# moth8_v1.net
KiCad netlist of a schematic drawn in EAGLE
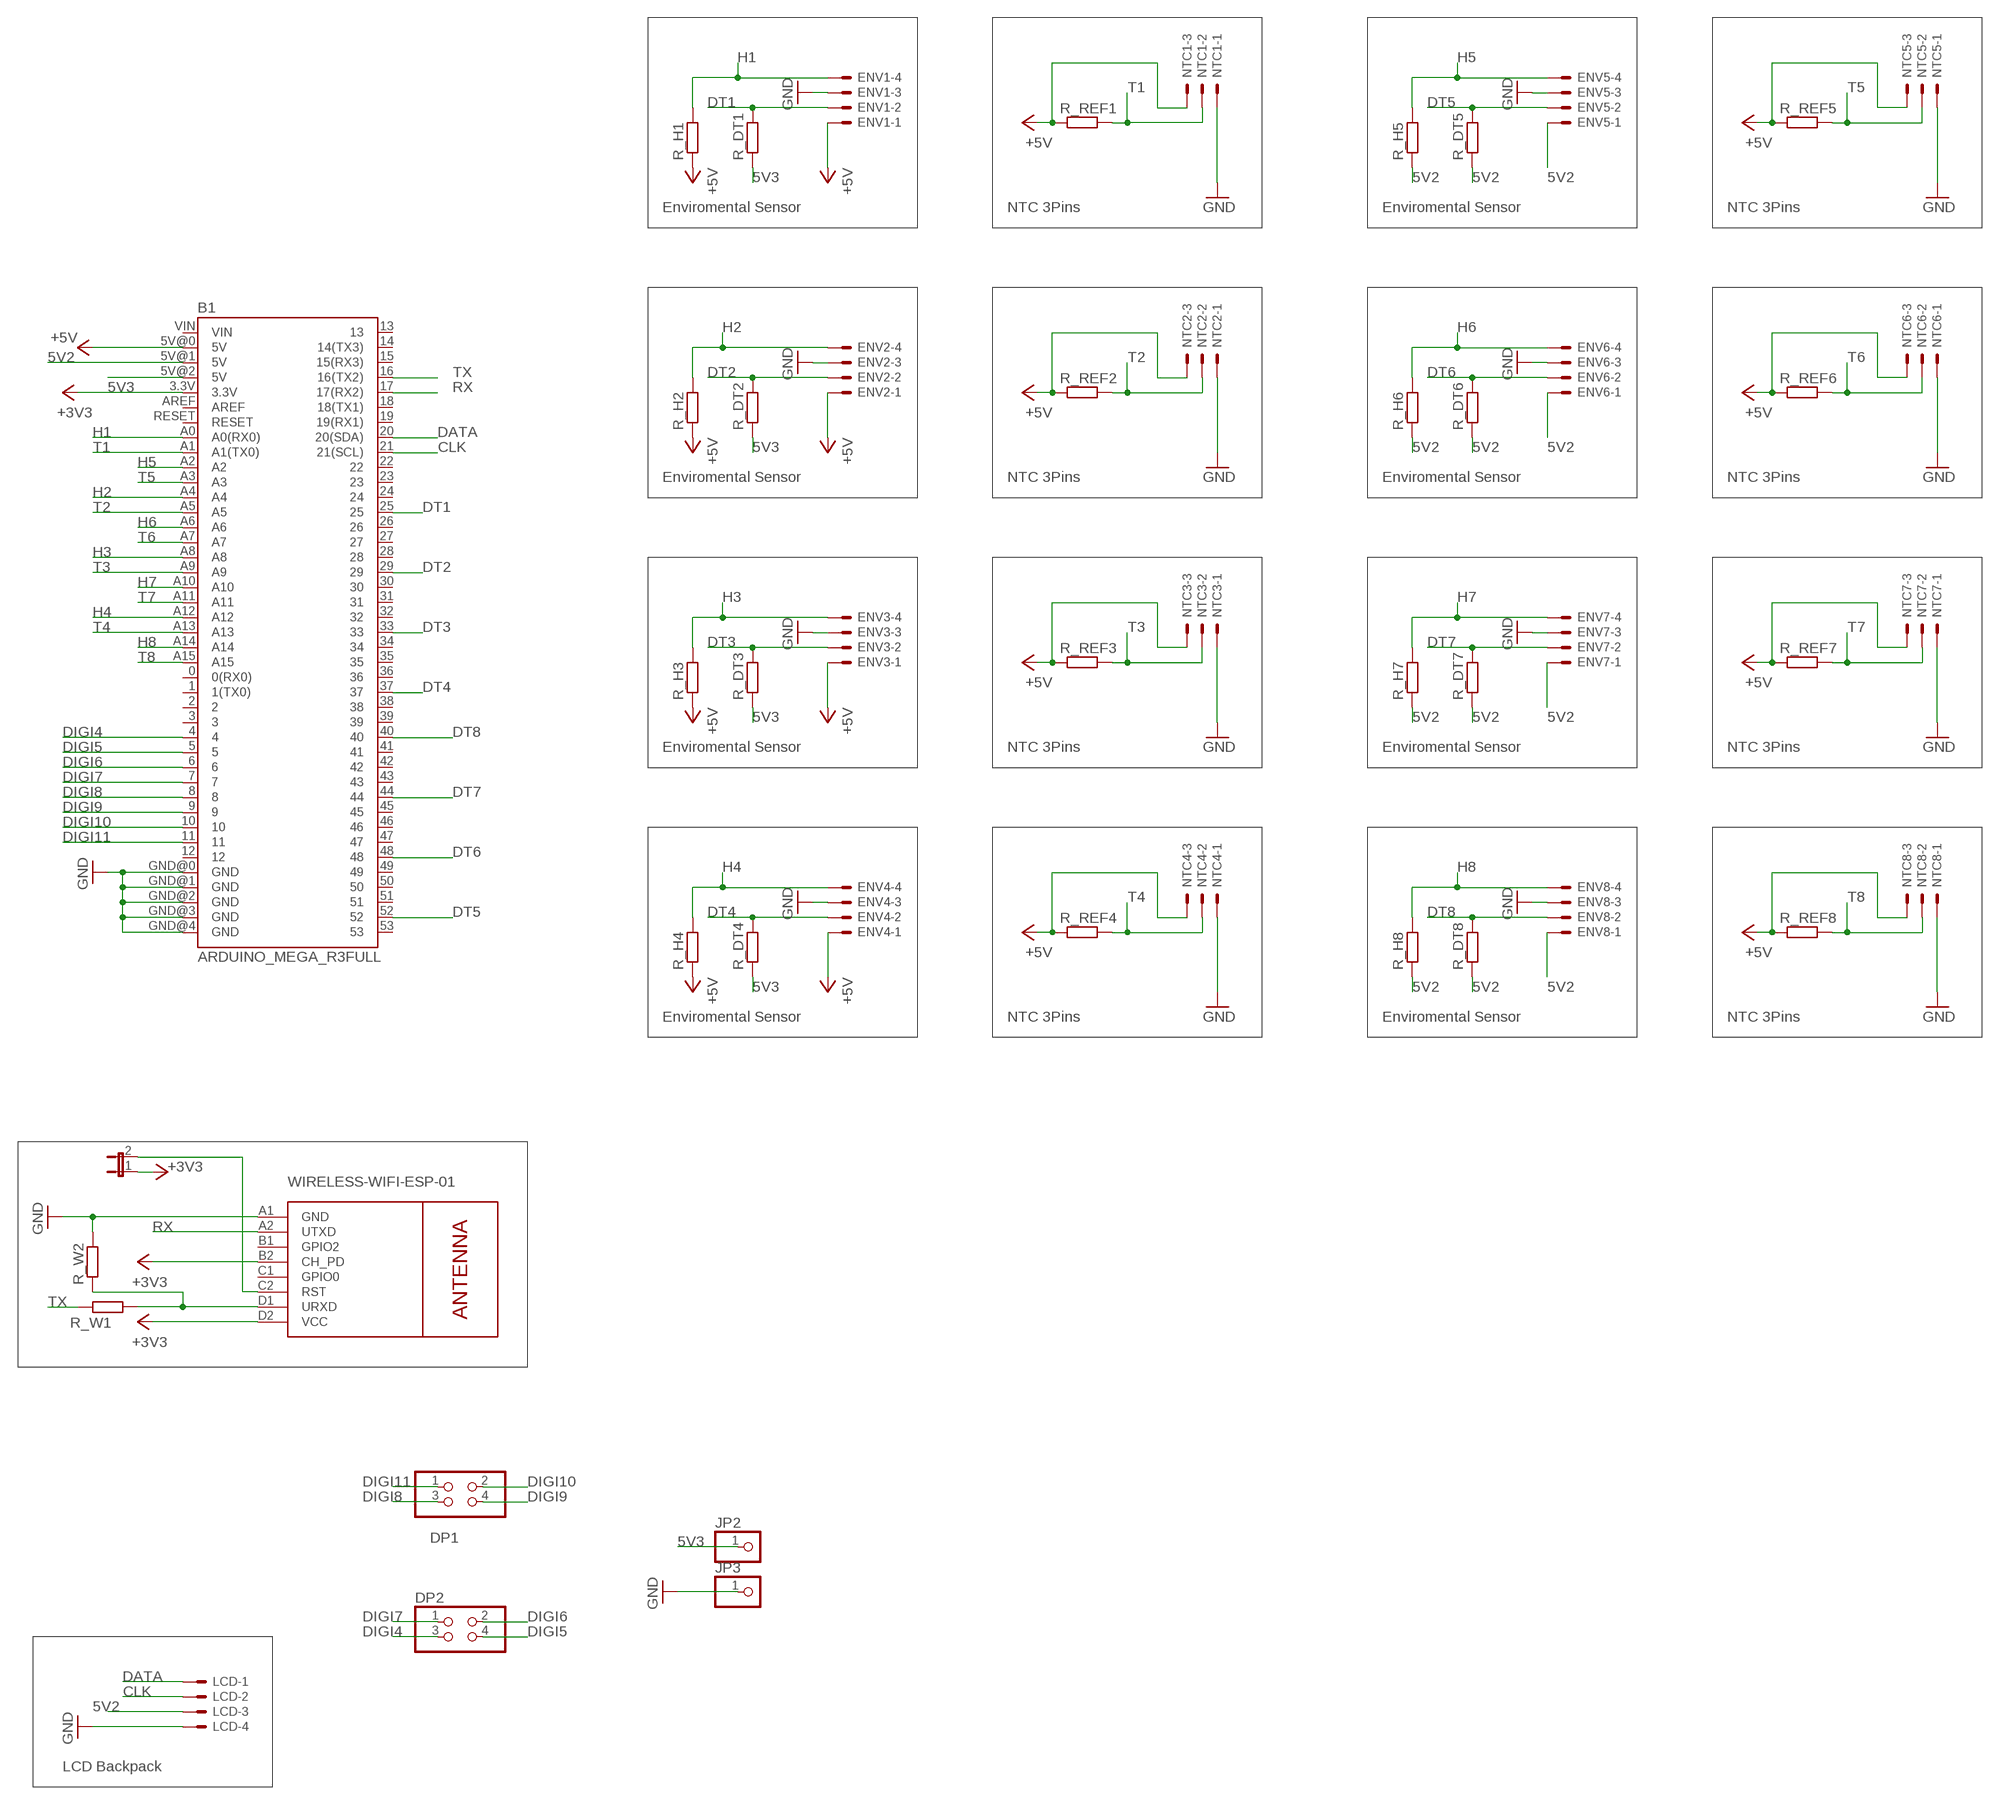
[diagram p0: schematic, sheet 1]

(export (version "E")
  (design (tool "Eeschema 10.0.6"))
  (components
    (comp (ref "B1")
      (value "ARDUINO_MEGA_R3FULL")
      (footprint "eagle-import:ARDUINO_MEGA")
      (libsource (lib "eagle-import") (part "ARDUINO_MEGA_R3FULL"))
    )
    (comp (ref "DP1")
      (value "PINHD-2X2")
      (footprint "eagle-import:2X02")
      (libsource (lib "eagle-import") (part "PINHD-2X2"))
    )
    (comp (ref "DP2")
      (value "PINHD-2X2")
      (footprint "eagle-import:2X02")
      (libsource (lib "eagle-import") (part "PINHD-2X2"))
    )
    (comp (ref "ENV1")
      (value "22-27-2041-04")
      (footprint "eagle-import:6410-04")
      (fields (field (name "MF") "MOLEX"))
      (libsource (lib "eagle-import") (part "22-?-0427-2041"))
    )
    (comp (ref "ENV2")
      (value "22-27-2041-04")
      (footprint "eagle-import:6410-04")
      (fields (field (name "MF") "MOLEX"))
      (libsource (lib "eagle-import") (part "22-?-0427-2041"))
    )
    (comp (ref "ENV3")
      (value "22-27-2041-04")
      (footprint "eagle-import:6410-04")
      (fields (field (name "MF") "MOLEX"))
      (libsource (lib "eagle-import") (part "22-?-0427-2041"))
    )
    (comp (ref "ENV4")
      (value "22-27-2041-04")
      (footprint "eagle-import:6410-04")
      (fields (field (name "MF") "MOLEX"))
      (libsource (lib "eagle-import") (part "22-?-0427-2041"))
    )
    (comp (ref "ENV5")
      (value "22-27-2041-04")
      (footprint "eagle-import:6410-04")
      (fields (field (name "MF") "MOLEX"))
      (libsource (lib "eagle-import") (part "22-?-0427-2041"))
    )
    (comp (ref "ENV6")
      (value "22-27-2041-04")
      (footprint "eagle-import:6410-04")
      (fields (field (name "MF") "MOLEX"))
      (libsource (lib "eagle-import") (part "22-?-0427-2041"))
    )
    (comp (ref "ENV7")
      (value "22-27-2041-04")
      (footprint "eagle-import:6410-04")
      (fields (field (name "MF") "MOLEX"))
      (libsource (lib "eagle-import") (part "22-?-0427-2041"))
    )
    (comp (ref "ENV8")
      (value "22-27-2041-04")
      (footprint "eagle-import:6410-04")
      (fields (field (name "MF") "MOLEX"))
      (libsource (lib "eagle-import") (part "22-?-0427-2041"))
    )
    (comp (ref "ESP-01")
      (value "WIRELESS-WIFI-ESP-01")
      (footprint "eagle-import:WIRELESS-WIFI-ESP-01")
      (libsource (lib "eagle-import") (part "WIRELESS-WIFI-ESP-01"))
    )
    (comp (ref "JP1")
      (value "JP1E")
      (footprint "eagle-import:JP1")
      (libsource (lib "eagle-import") (part "JP1E"))
    )
    (comp (ref "JP2")
      (value "PINHD-1X1")
      (footprint "eagle-import:1X01")
      (libsource (lib "eagle-import") (part "PINHD-1X1"))
    )
    (comp (ref "JP3")
      (value "PINHD-1X1")
      (footprint "eagle-import:1X01")
      (libsource (lib "eagle-import") (part "PINHD-1X1"))
    )
    (comp (ref "LCD")
      (value "22-27-2041-04")
      (footprint "eagle-import:6410-04")
      (fields (field (name "MF") "MOLEX"))
      (libsource (lib "eagle-import") (part "22-?-0427-2041"))
    )
    (comp (ref "NTC1")
      (value "22-27-2031-03")
      (footprint "eagle-import:6410-03")
      (fields (field (name "MF") "MOLEX"))
      (libsource (lib "eagle-import") (part "22-?-0327-2031"))
    )
    (comp (ref "NTC2")
      (value "22-27-2031-03")
      (footprint "eagle-import:6410-03")
      (fields (field (name "MF") "MOLEX"))
      (libsource (lib "eagle-import") (part "22-?-0327-2031"))
    )
    (comp (ref "NTC3")
      (value "22-27-2031-03")
      (footprint "eagle-import:6410-03")
      (fields (field (name "MF") "MOLEX"))
      (libsource (lib "eagle-import") (part "22-?-0327-2031"))
    )
    (comp (ref "NTC4")
      (value "22-27-2031-03")
      (footprint "eagle-import:6410-03")
      (fields (field (name "MF") "MOLEX"))
      (libsource (lib "eagle-import") (part "22-?-0327-2031"))
    )
    (comp (ref "NTC5")
      (value "22-27-2031-03")
      (footprint "eagle-import:6410-03")
      (fields (field (name "MF") "MOLEX"))
      (libsource (lib "eagle-import") (part "22-?-0327-2031"))
    )
    (comp (ref "NTC6")
      (value "22-27-2031-03")
      (footprint "eagle-import:6410-03")
      (fields (field (name "MF") "MOLEX"))
      (libsource (lib "eagle-import") (part "22-?-0327-2031"))
    )
    (comp (ref "NTC7")
      (value "22-27-2031-03")
      (footprint "eagle-import:6410-03")
      (fields (field (name "MF") "MOLEX"))
      (libsource (lib "eagle-import") (part "22-?-0327-2031"))
    )
    (comp (ref "NTC8")
      (value "22-27-2031-03")
      (footprint "eagle-import:6410-03")
      (fields (field (name "MF") "MOLEX"))
      (libsource (lib "eagle-import") (part "22-?-0327-2031"))
    )
    (comp (ref "R_DT1")
      (value "R-EU_R1206")
      (footprint "eagle-import:R1206")
      (libsource (lib "eagle-import") (part "R-EU_R1206"))
    )
    (comp (ref "R_DT2")
      (value "R-EU_R1206")
      (footprint "eagle-import:R1206")
      (libsource (lib "eagle-import") (part "R-EU_R1206"))
    )
    (comp (ref "R_DT3")
      (value "R-EU_R1206")
      (footprint "eagle-import:R1206")
      (libsource (lib "eagle-import") (part "R-EU_R1206"))
    )
    (comp (ref "R_DT4")
      (value "R-EU_R1206")
      (footprint "eagle-import:R1206")
      (libsource (lib "eagle-import") (part "R-EU_R1206"))
    )
    (comp (ref "R_DT5")
      (value "R-EU_R1206")
      (footprint "eagle-import:R1206")
      (libsource (lib "eagle-import") (part "R-EU_R1206"))
    )
    (comp (ref "R_DT6")
      (value "R-EU_R1206")
      (footprint "eagle-import:R1206")
      (libsource (lib "eagle-import") (part "R-EU_R1206"))
    )
    (comp (ref "R_DT7")
      (value "R-EU_R1206")
      (footprint "eagle-import:R1206")
      (libsource (lib "eagle-import") (part "R-EU_R1206"))
    )
    (comp (ref "R_DT8")
      (value "R-EU_R1206")
      (footprint "eagle-import:R1206")
      (libsource (lib "eagle-import") (part "R-EU_R1206"))
    )
    (comp (ref "R_H1")
      (value "R-EU_R1206")
      (footprint "eagle-import:R1206")
      (libsource (lib "eagle-import") (part "R-EU_R1206"))
    )
    (comp (ref "R_H2")
      (value "R-EU_R1206")
      (footprint "eagle-import:R1206")
      (libsource (lib "eagle-import") (part "R-EU_R1206"))
    )
    (comp (ref "R_H3")
      (value "R-EU_R1206")
      (footprint "eagle-import:R1206")
      (libsource (lib "eagle-import") (part "R-EU_R1206"))
    )
    (comp (ref "R_H4")
      (value "R-EU_R1206")
      (footprint "eagle-import:R1206")
      (libsource (lib "eagle-import") (part "R-EU_R1206"))
    )
    (comp (ref "R_H5")
      (value "R-EU_R1206")
      (footprint "eagle-import:R1206")
      (libsource (lib "eagle-import") (part "R-EU_R1206"))
    )
    (comp (ref "R_H6")
      (value "R-EU_R1206")
      (footprint "eagle-import:R1206")
      (libsource (lib "eagle-import") (part "R-EU_R1206"))
    )
    (comp (ref "R_H7")
      (value "R-EU_R1206")
      (footprint "eagle-import:R1206")
      (libsource (lib "eagle-import") (part "R-EU_R1206"))
    )
    (comp (ref "R_H8")
      (value "R-EU_R1206")
      (footprint "eagle-import:R1206")
      (libsource (lib "eagle-import") (part "R-EU_R1206"))
    )
    (comp (ref "R_REF1")
      (value "R-EU_R1206")
      (footprint "eagle-import:R1206")
      (libsource (lib "eagle-import") (part "R-EU_R1206"))
    )
    (comp (ref "R_REF2")
      (value "R-EU_R1206")
      (footprint "eagle-import:R1206")
      (libsource (lib "eagle-import") (part "R-EU_R1206"))
    )
    (comp (ref "R_REF3")
      (value "R-EU_R1206")
      (footprint "eagle-import:R1206")
      (libsource (lib "eagle-import") (part "R-EU_R1206"))
    )
    (comp (ref "R_REF4")
      (value "R-EU_R1206")
      (footprint "eagle-import:R1206")
      (libsource (lib "eagle-import") (part "R-EU_R1206"))
    )
    (comp (ref "R_REF5")
      (value "R-EU_R1206")
      (footprint "eagle-import:R1206")
      (libsource (lib "eagle-import") (part "R-EU_R1206"))
    )
    (comp (ref "R_REF6")
      (value "R-EU_R1206")
      (footprint "eagle-import:R1206")
      (libsource (lib "eagle-import") (part "R-EU_R1206"))
    )
    (comp (ref "R_REF7")
      (value "R-EU_R1206")
      (footprint "eagle-import:R1206")
      (libsource (lib "eagle-import") (part "R-EU_R1206"))
    )
    (comp (ref "R_REF8")
      (value "R-EU_R1206")
      (footprint "eagle-import:R1206")
      (libsource (lib "eagle-import") (part "R-EU_R1206"))
    )
    (comp (ref "R_W1")
      (value "R-EU_R1206")
      (footprint "eagle-import:R1206")
      (libsource (lib "eagle-import") (part "R-EU_R1206"))
    )
    (comp (ref "R_W2")
      (value "R-EU_R1206")
      (footprint "eagle-import:R1206")
      (libsource (lib "eagle-import") (part "R-EU_R1206"))
    )
  )
  (nets
    (net (code "1") (name "+3V3") (class "Default")
      (node (ref "B1") (pin "3.3V") (pinfunction "3.3V_3.3V") (pintype "bidirectional"))
      (node (ref "ESP-01") (pin "B2") (pinfunction "CH_PD_B2") (pintype "bidirectional"))
      (node (ref "ESP-01") (pin "D2") (pinfunction "VCC_D2") (pintype "power_in"))
      (node (ref "JP1") (pin "1") (pinfunction "1_1") (pintype "passive"))
    )
    (net (code "2") (name "+5V") (class "Default")
      (node (ref "B1") (pin "5V@0") (pinfunction "5V_5V@0") (pintype "bidirectional"))
      (node (ref "ENV1") (pin "1") (pinfunction "S_1") (pintype "passive"))
      (node (ref "ENV2") (pin "1") (pinfunction "S_1") (pintype "passive"))
      (node (ref "ENV3") (pin "1") (pinfunction "S_1") (pintype "passive"))
      (node (ref "ENV4") (pin "1") (pinfunction "S_1") (pintype "passive"))
      (node (ref "NTC1") (pin "3") (pinfunction "S_3") (pintype "passive"))
      (node (ref "NTC2") (pin "3") (pinfunction "S_3") (pintype "passive"))
      (node (ref "NTC3") (pin "3") (pinfunction "S_3") (pintype "passive"))
      (node (ref "NTC4") (pin "3") (pinfunction "S_3") (pintype "passive"))
      (node (ref "NTC5") (pin "3") (pinfunction "S_3") (pintype "passive"))
      (node (ref "NTC6") (pin "3") (pinfunction "S_3") (pintype "passive"))
      (node (ref "NTC7") (pin "3") (pinfunction "S_3") (pintype "passive"))
      (node (ref "NTC8") (pin "3") (pinfunction "S_3") (pintype "passive"))
      (node (ref "R_H1") (pin "1") (pinfunction "1_1") (pintype "passive"))
      (node (ref "R_H2") (pin "1") (pinfunction "1_1") (pintype "passive"))
      (node (ref "R_H3") (pin "1") (pinfunction "1_1") (pintype "passive"))
      (node (ref "R_H4") (pin "1") (pinfunction "1_1") (pintype "passive"))
      (node (ref "R_REF1") (pin "1") (pinfunction "1_1") (pintype "passive"))
      (node (ref "R_REF2") (pin "1") (pinfunction "1_1") (pintype "passive"))
      (node (ref "R_REF3") (pin "1") (pinfunction "1_1") (pintype "passive"))
      (node (ref "R_REF4") (pin "1") (pinfunction "1_1") (pintype "passive"))
      (node (ref "R_REF5") (pin "1") (pinfunction "1_1") (pintype "passive"))
      (node (ref "R_REF6") (pin "1") (pinfunction "1_1") (pintype "passive"))
      (node (ref "R_REF7") (pin "1") (pinfunction "1_1") (pintype "passive"))
      (node (ref "R_REF8") (pin "1") (pinfunction "1_1") (pintype "passive"))
    )
    (net (code "3") (name "/5V2") (class "Default")
      (node (ref "B1") (pin "5V@1") (pinfunction "5V_5V@1") (pintype "bidirectional"))
      (node (ref "ENV5") (pin "1") (pinfunction "S_1") (pintype "passive"))
      (node (ref "ENV6") (pin "1") (pinfunction "S_1") (pintype "passive"))
      (node (ref "ENV7") (pin "1") (pinfunction "S_1") (pintype "passive"))
      (node (ref "ENV8") (pin "1") (pinfunction "S_1") (pintype "passive"))
      (node (ref "LCD") (pin "3") (pinfunction "S_3") (pintype "passive"))
      (node (ref "R_DT5") (pin "1") (pinfunction "1_1") (pintype "passive"))
      (node (ref "R_DT6") (pin "1") (pinfunction "1_1") (pintype "passive"))
      (node (ref "R_DT7") (pin "1") (pinfunction "1_1") (pintype "passive"))
      (node (ref "R_DT8") (pin "1") (pinfunction "1_1") (pintype "passive"))
      (node (ref "R_H5") (pin "1") (pinfunction "1_1") (pintype "passive"))
      (node (ref "R_H6") (pin "1") (pinfunction "1_1") (pintype "passive"))
      (node (ref "R_H7") (pin "1") (pinfunction "1_1") (pintype "passive"))
      (node (ref "R_H8") (pin "1") (pinfunction "1_1") (pintype "passive"))
    )
    (net (code "4") (name "/5V3") (class "Default")
      (node (ref "B1") (pin "5V@2") (pinfunction "5V_5V@2") (pintype "bidirectional"))
      (node (ref "JP2") (pin "1") (pinfunction "1_1") (pintype "passive"))
      (node (ref "R_DT1") (pin "1") (pinfunction "1_1") (pintype "passive"))
      (node (ref "R_DT2") (pin "1") (pinfunction "1_1") (pintype "passive"))
      (node (ref "R_DT3") (pin "1") (pinfunction "1_1") (pintype "passive"))
      (node (ref "R_DT4") (pin "1") (pinfunction "1_1") (pintype "passive"))
    )
    (net (code "5") (name "/CLK") (class "Default")
      (node (ref "B1") (pin "21") (pinfunction "21(SCL)_21") (pintype "bidirectional"))
      (node (ref "LCD") (pin "2") (pinfunction "S_2") (pintype "passive"))
    )
    (net (code "6") (name "/DATA") (class "Default")
      (node (ref "B1") (pin "20") (pinfunction "20(SDA)_20") (pintype "bidirectional"))
      (node (ref "LCD") (pin "1") (pinfunction "S_1") (pintype "passive"))
    )
    (net (code "7") (name "/DIGI4") (class "Default")
      (node (ref "B1") (pin "4") (pinfunction "4_4") (pintype "bidirectional"))
      (node (ref "DP2") (pin "3") (pinfunction "3_3") (pintype "passive"))
    )
    (net (code "8") (name "/DIGI5") (class "Default")
      (node (ref "B1") (pin "5") (pinfunction "5_5") (pintype "bidirectional"))
      (node (ref "DP2") (pin "4") (pinfunction "4_4") (pintype "passive"))
    )
    (net (code "9") (name "/DIGI6") (class "Default")
      (node (ref "B1") (pin "6") (pinfunction "6_6") (pintype "bidirectional"))
      (node (ref "DP2") (pin "2") (pinfunction "2_2") (pintype "passive"))
    )
    (net (code "10") (name "/DIGI7") (class "Default")
      (node (ref "B1") (pin "7") (pinfunction "7_7") (pintype "bidirectional"))
      (node (ref "DP2") (pin "1") (pinfunction "1_1") (pintype "passive"))
    )
    (net (code "11") (name "/DIGI8") (class "Default")
      (node (ref "B1") (pin "8") (pinfunction "8_8") (pintype "bidirectional"))
      (node (ref "DP1") (pin "3") (pinfunction "3_3") (pintype "passive"))
    )
    (net (code "12") (name "/DIGI9") (class "Default")
      (node (ref "B1") (pin "9") (pinfunction "9_9") (pintype "bidirectional"))
      (node (ref "DP1") (pin "4") (pinfunction "4_4") (pintype "passive"))
    )
    (net (code "13") (name "/DIGI10") (class "Default")
      (node (ref "B1") (pin "10") (pinfunction "10_10") (pintype "bidirectional"))
      (node (ref "DP1") (pin "2") (pinfunction "2_2") (pintype "passive"))
    )
    (net (code "14") (name "/DIGI11") (class "Default")
      (node (ref "B1") (pin "11") (pinfunction "11_11") (pintype "bidirectional"))
      (node (ref "DP1") (pin "1") (pinfunction "1_1") (pintype "passive"))
    )
    (net (code "15") (name "/DT1") (class "Default")
      (node (ref "B1") (pin "25") (pinfunction "25_25") (pintype "bidirectional"))
      (node (ref "ENV1") (pin "2") (pinfunction "S_2") (pintype "passive"))
      (node (ref "R_DT1") (pin "2") (pinfunction "2_2") (pintype "passive"))
    )
    (net (code "16") (name "/DT2") (class "Default")
      (node (ref "B1") (pin "29") (pinfunction "29_29") (pintype "bidirectional"))
      (node (ref "ENV2") (pin "2") (pinfunction "S_2") (pintype "passive"))
      (node (ref "R_DT2") (pin "2") (pinfunction "2_2") (pintype "passive"))
    )
    (net (code "17") (name "/DT3") (class "Default")
      (node (ref "B1") (pin "33") (pinfunction "33_33") (pintype "bidirectional"))
      (node (ref "ENV3") (pin "2") (pinfunction "S_2") (pintype "passive"))
      (node (ref "R_DT3") (pin "2") (pinfunction "2_2") (pintype "passive"))
    )
    (net (code "18") (name "/DT4") (class "Default")
      (node (ref "B1") (pin "37") (pinfunction "37_37") (pintype "bidirectional"))
      (node (ref "ENV4") (pin "2") (pinfunction "S_2") (pintype "passive"))
      (node (ref "R_DT4") (pin "2") (pinfunction "2_2") (pintype "passive"))
    )
    (net (code "19") (name "/DT5") (class "Default")
      (node (ref "B1") (pin "52") (pinfunction "52_52") (pintype "bidirectional"))
      (node (ref "ENV5") (pin "2") (pinfunction "S_2") (pintype "passive"))
      (node (ref "R_DT5") (pin "2") (pinfunction "2_2") (pintype "passive"))
    )
    (net (code "20") (name "/DT6") (class "Default")
      (node (ref "B1") (pin "48") (pinfunction "48_48") (pintype "bidirectional"))
      (node (ref "ENV6") (pin "2") (pinfunction "S_2") (pintype "passive"))
      (node (ref "R_DT6") (pin "2") (pinfunction "2_2") (pintype "passive"))
    )
    (net (code "21") (name "/DT7") (class "Default")
      (node (ref "B1") (pin "44") (pinfunction "44_44") (pintype "bidirectional"))
      (node (ref "ENV7") (pin "2") (pinfunction "S_2") (pintype "passive"))
      (node (ref "R_DT7") (pin "2") (pinfunction "2_2") (pintype "passive"))
    )
    (net (code "22") (name "/DT8") (class "Default")
      (node (ref "B1") (pin "40") (pinfunction "40_40") (pintype "bidirectional"))
      (node (ref "ENV8") (pin "2") (pinfunction "S_2") (pintype "passive"))
      (node (ref "R_DT8") (pin "2") (pinfunction "2_2") (pintype "passive"))
    )
    (net (code "23") (name "/H1") (class "Default")
      (node (ref "B1") (pin "A0") (pinfunction "A0(RX0)_A0") (pintype "bidirectional"))
      (node (ref "ENV1") (pin "4") (pinfunction "S_4") (pintype "passive"))
      (node (ref "R_H1") (pin "2") (pinfunction "2_2") (pintype "passive"))
    )
    (net (code "24") (name "/H2") (class "Default")
      (node (ref "B1") (pin "A4") (pinfunction "A4_A4") (pintype "bidirectional"))
      (node (ref "ENV2") (pin "4") (pinfunction "S_4") (pintype "passive"))
      (node (ref "R_H2") (pin "2") (pinfunction "2_2") (pintype "passive"))
    )
    (net (code "25") (name "/H3") (class "Default")
      (node (ref "B1") (pin "A8") (pinfunction "A8_A8") (pintype "bidirectional"))
      (node (ref "ENV3") (pin "4") (pinfunction "S_4") (pintype "passive"))
      (node (ref "R_H3") (pin "2") (pinfunction "2_2") (pintype "passive"))
    )
    (net (code "26") (name "/H4") (class "Default")
      (node (ref "B1") (pin "A12") (pinfunction "A12_A12") (pintype "bidirectional"))
      (node (ref "ENV4") (pin "4") (pinfunction "S_4") (pintype "passive"))
      (node (ref "R_H4") (pin "2") (pinfunction "2_2") (pintype "passive"))
    )
    (net (code "27") (name "/H5") (class "Default")
      (node (ref "B1") (pin "A2") (pinfunction "A2_A2") (pintype "bidirectional"))
      (node (ref "ENV5") (pin "4") (pinfunction "S_4") (pintype "passive"))
      (node (ref "R_H5") (pin "2") (pinfunction "2_2") (pintype "passive"))
    )
    (net (code "28") (name "/H6") (class "Default")
      (node (ref "B1") (pin "A6") (pinfunction "A6_A6") (pintype "bidirectional"))
      (node (ref "ENV6") (pin "4") (pinfunction "S_4") (pintype "passive"))
      (node (ref "R_H6") (pin "2") (pinfunction "2_2") (pintype "passive"))
    )
    (net (code "29") (name "/H7") (class "Default")
      (node (ref "B1") (pin "A10") (pinfunction "A10_A10") (pintype "bidirectional"))
      (node (ref "ENV7") (pin "4") (pinfunction "S_4") (pintype "passive"))
      (node (ref "R_H7") (pin "2") (pinfunction "2_2") (pintype "passive"))
    )
    (net (code "30") (name "/H8") (class "Default")
      (node (ref "B1") (pin "A14") (pinfunction "A14_A14") (pintype "bidirectional"))
      (node (ref "ENV8") (pin "4") (pinfunction "S_4") (pintype "passive"))
      (node (ref "R_H8") (pin "2") (pinfunction "2_2") (pintype "passive"))
    )
    (net (code "31") (name "/RX") (class "Default")
      (node (ref "B1") (pin "17") (pinfunction "17(RX2)_17") (pintype "bidirectional"))
      (node (ref "ESP-01") (pin "A2") (pinfunction "UTXD_A2") (pintype "bidirectional"))
    )
    (net (code "32") (name "/T1") (class "Default")
      (node (ref "B1") (pin "A1") (pinfunction "A1(TX0)_A1") (pintype "bidirectional"))
      (node (ref "NTC1") (pin "2") (pinfunction "S_2") (pintype "passive"))
      (node (ref "R_REF1") (pin "2") (pinfunction "2_2") (pintype "passive"))
    )
    (net (code "33") (name "/T2") (class "Default")
      (node (ref "B1") (pin "A5") (pinfunction "A5_A5") (pintype "bidirectional"))
      (node (ref "NTC2") (pin "2") (pinfunction "S_2") (pintype "passive"))
      (node (ref "R_REF2") (pin "2") (pinfunction "2_2") (pintype "passive"))
    )
    (net (code "34") (name "/T3") (class "Default")
      (node (ref "B1") (pin "A9") (pinfunction "A9_A9") (pintype "bidirectional"))
      (node (ref "NTC3") (pin "2") (pinfunction "S_2") (pintype "passive"))
      (node (ref "R_REF3") (pin "2") (pinfunction "2_2") (pintype "passive"))
    )
    (net (code "35") (name "/T4") (class "Default")
      (node (ref "B1") (pin "A13") (pinfunction "A13_A13") (pintype "bidirectional"))
      (node (ref "NTC4") (pin "2") (pinfunction "S_2") (pintype "passive"))
      (node (ref "R_REF4") (pin "2") (pinfunction "2_2") (pintype "passive"))
    )
    (net (code "36") (name "/T5") (class "Default")
      (node (ref "B1") (pin "A3") (pinfunction "A3_A3") (pintype "bidirectional"))
      (node (ref "NTC5") (pin "2") (pinfunction "S_2") (pintype "passive"))
      (node (ref "R_REF5") (pin "2") (pinfunction "2_2") (pintype "passive"))
    )
    (net (code "37") (name "/T6") (class "Default")
      (node (ref "B1") (pin "A7") (pinfunction "A7_A7") (pintype "bidirectional"))
      (node (ref "NTC6") (pin "2") (pinfunction "S_2") (pintype "passive"))
      (node (ref "R_REF6") (pin "2") (pinfunction "2_2") (pintype "passive"))
    )
    (net (code "38") (name "/T7") (class "Default")
      (node (ref "B1") (pin "A11") (pinfunction "A11_A11") (pintype "bidirectional"))
      (node (ref "NTC7") (pin "2") (pinfunction "S_2") (pintype "passive"))
      (node (ref "R_REF7") (pin "2") (pinfunction "2_2") (pintype "passive"))
    )
    (net (code "39") (name "/T8") (class "Default")
      (node (ref "B1") (pin "A15") (pinfunction "A15_A15") (pintype "bidirectional"))
      (node (ref "NTC8") (pin "2") (pinfunction "S_2") (pintype "passive"))
      (node (ref "R_REF8") (pin "2") (pinfunction "2_2") (pintype "passive"))
    )
    (net (code "40") (name "/TX") (class "Default")
      (node (ref "B1") (pin "16") (pinfunction "16(TX2)_16") (pintype "bidirectional"))
      (node (ref "R_W1") (pin "1") (pinfunction "1_1") (pintype "passive"))
    )
    (net (code "41") (name "GND") (class "Default")
      (node (ref "B1") (pin "GND@0") (pinfunction "GND_GND@0") (pintype "bidirectional"))
      (node (ref "B1") (pin "GND@1") (pinfunction "GND_GND@1") (pintype "bidirectional"))
      (node (ref "B1") (pin "GND@2") (pinfunction "GND_GND@2") (pintype "bidirectional"))
      (node (ref "B1") (pin "GND@3") (pinfunction "GND_GND@3") (pintype "bidirectional"))
      (node (ref "B1") (pin "GND@4") (pinfunction "GND_GND@4") (pintype "bidirectional"))
      (node (ref "ENV1") (pin "3") (pinfunction "S_3") (pintype "passive"))
      (node (ref "ENV2") (pin "3") (pinfunction "S_3") (pintype "passive"))
      (node (ref "ENV3") (pin "3") (pinfunction "S_3") (pintype "passive"))
      (node (ref "ENV4") (pin "3") (pinfunction "S_3") (pintype "passive"))
      (node (ref "ENV5") (pin "3") (pinfunction "S_3") (pintype "passive"))
      (node (ref "ENV6") (pin "3") (pinfunction "S_3") (pintype "passive"))
      (node (ref "ENV7") (pin "3") (pinfunction "S_3") (pintype "passive"))
      (node (ref "ENV8") (pin "3") (pinfunction "S_3") (pintype "passive"))
      (node (ref "ESP-01") (pin "A1") (pinfunction "GND_A1") (pintype "power_in"))
      (node (ref "JP3") (pin "1") (pinfunction "1_1") (pintype "passive"))
      (node (ref "LCD") (pin "4") (pinfunction "S_4") (pintype "passive"))
      (node (ref "NTC1") (pin "1") (pinfunction "S_1") (pintype "passive"))
      (node (ref "NTC2") (pin "1") (pinfunction "S_1") (pintype "passive"))
      (node (ref "NTC3") (pin "1") (pinfunction "S_1") (pintype "passive"))
      (node (ref "NTC4") (pin "1") (pinfunction "S_1") (pintype "passive"))
      (node (ref "NTC5") (pin "1") (pinfunction "S_1") (pintype "passive"))
      (node (ref "NTC6") (pin "1") (pinfunction "S_1") (pintype "passive"))
      (node (ref "NTC7") (pin "1") (pinfunction "S_1") (pintype "passive"))
      (node (ref "NTC8") (pin "1") (pinfunction "S_1") (pintype "passive"))
      (node (ref "R_W2") (pin "2") (pinfunction "2_2") (pintype "passive"))
    )
    (net (code "42") (name "Net-(ESP-01-RST)") (class "Default")
      (node (ref "ESP-01") (pin "C2") (pinfunction "RST_C2") (pintype "bidirectional"))
      (node (ref "JP1") (pin "2") (pinfunction "2_2") (pintype "passive"))
    )
    (net (code "43") (name "Net-(ESP-01-URXD)") (class "Default")
      (node (ref "ESP-01") (pin "D1") (pinfunction "URXD_D1") (pintype "bidirectional"))
      (node (ref "R_W1") (pin "2") (pinfunction "2_2") (pintype "passive"))
      (node (ref "R_W2") (pin "1") (pinfunction "1_1") (pintype "passive"))
    )
    (net (code "44") (name "unconnected-(B1-0(RX0)-Pad0)") (class "Default")
      (node (ref "B1") (pin "0") (pinfunction "0(RX0)_0") (pintype "bidirectional"))
    )
    (net (code "45") (name "unconnected-(B1-1(TX0)-Pad1)") (class "Default")
      (node (ref "B1") (pin "1") (pinfunction "1(TX0)_1") (pintype "bidirectional"))
    )
    (net (code "46") (name "unconnected-(B1-14(TX3)-Pad14)") (class "Default")
      (node (ref "B1") (pin "14") (pinfunction "14(TX3)_14") (pintype "bidirectional"))
    )
    (net (code "47") (name "unconnected-(B1-15(RX3)-Pad15)") (class "Default")
      (node (ref "B1") (pin "15") (pinfunction "15(RX3)_15") (pintype "bidirectional"))
    )
    (net (code "48") (name "unconnected-(B1-18(TX1)-Pad18)") (class "Default")
      (node (ref "B1") (pin "18") (pinfunction "18(TX1)_18") (pintype "bidirectional"))
    )
    (net (code "49") (name "unconnected-(B1-19(RX1)-Pad19)") (class "Default")
      (node (ref "B1") (pin "19") (pinfunction "19(RX1)_19") (pintype "bidirectional"))
    )
    (net (code "50") (name "unconnected-(B1-Pad2)") (class "Default")
      (node (ref "B1") (pin "2") (pinfunction "2_2") (pintype "bidirectional"))
    )
    (net (code "51") (name "unconnected-(B1-Pad3)") (class "Default")
      (node (ref "B1") (pin "3") (pinfunction "3_3") (pintype "bidirectional"))
    )
    (net (code "52") (name "unconnected-(B1-Pad12)") (class "Default")
      (node (ref "B1") (pin "12") (pinfunction "12_12") (pintype "bidirectional"))
    )
    (net (code "53") (name "unconnected-(B1-Pad13)") (class "Default")
      (node (ref "B1") (pin "13") (pinfunction "13_13") (pintype "bidirectional"))
    )
    (net (code "54") (name "unconnected-(B1-Pad22)") (class "Default")
      (node (ref "B1") (pin "22") (pinfunction "22_22") (pintype "bidirectional"))
    )
    (net (code "55") (name "unconnected-(B1-Pad23)") (class "Default")
      (node (ref "B1") (pin "23") (pinfunction "23_23") (pintype "bidirectional"))
    )
    (net (code "56") (name "unconnected-(B1-Pad24)") (class "Default")
      (node (ref "B1") (pin "24") (pinfunction "24_24") (pintype "bidirectional"))
    )
    (net (code "57") (name "unconnected-(B1-Pad26)") (class "Default")
      (node (ref "B1") (pin "26") (pinfunction "26_26") (pintype "bidirectional"))
    )
    (net (code "58") (name "unconnected-(B1-Pad27)") (class "Default")
      (node (ref "B1") (pin "27") (pinfunction "27_27") (pintype "bidirectional"))
    )
    (net (code "59") (name "unconnected-(B1-Pad28)") (class "Default")
      (node (ref "B1") (pin "28") (pinfunction "28_28") (pintype "bidirectional"))
    )
    (net (code "60") (name "unconnected-(B1-Pad30)") (class "Default")
      (node (ref "B1") (pin "30") (pinfunction "30_30") (pintype "bidirectional"))
    )
    (net (code "61") (name "unconnected-(B1-Pad31)") (class "Default")
      (node (ref "B1") (pin "31") (pinfunction "31_31") (pintype "bidirectional"))
    )
    (net (code "62") (name "unconnected-(B1-Pad32)") (class "Default")
      (node (ref "B1") (pin "32") (pinfunction "32_32") (pintype "bidirectional"))
    )
    (net (code "63") (name "unconnected-(B1-Pad34)") (class "Default")
      (node (ref "B1") (pin "34") (pinfunction "34_34") (pintype "bidirectional"))
    )
    (net (code "64") (name "unconnected-(B1-Pad35)") (class "Default")
      (node (ref "B1") (pin "35") (pinfunction "35_35") (pintype "bidirectional"))
    )
    (net (code "65") (name "unconnected-(B1-Pad36)") (class "Default")
      (node (ref "B1") (pin "36") (pinfunction "36_36") (pintype "bidirectional"))
    )
    (net (code "66") (name "unconnected-(B1-Pad38)") (class "Default")
      (node (ref "B1") (pin "38") (pinfunction "38_38") (pintype "bidirectional"))
    )
    (net (code "67") (name "unconnected-(B1-Pad39)") (class "Default")
      (node (ref "B1") (pin "39") (pinfunction "39_39") (pintype "bidirectional"))
    )
    (net (code "68") (name "unconnected-(B1-Pad41)") (class "Default")
      (node (ref "B1") (pin "41") (pinfunction "41_41") (pintype "bidirectional"))
    )
    (net (code "69") (name "unconnected-(B1-Pad42)") (class "Default")
      (node (ref "B1") (pin "42") (pinfunction "42_42") (pintype "bidirectional"))
    )
    (net (code "70") (name "unconnected-(B1-Pad43)") (class "Default")
      (node (ref "B1") (pin "43") (pinfunction "43_43") (pintype "bidirectional"))
    )
    (net (code "71") (name "unconnected-(B1-Pad45)") (class "Default")
      (node (ref "B1") (pin "45") (pinfunction "45_45") (pintype "bidirectional"))
    )
    (net (code "72") (name "unconnected-(B1-Pad46)") (class "Default")
      (node (ref "B1") (pin "46") (pinfunction "46_46") (pintype "bidirectional"))
    )
    (net (code "73") (name "unconnected-(B1-Pad47)") (class "Default")
      (node (ref "B1") (pin "47") (pinfunction "47_47") (pintype "bidirectional"))
    )
    (net (code "74") (name "unconnected-(B1-Pad49)") (class "Default")
      (node (ref "B1") (pin "49") (pinfunction "49_49") (pintype "bidirectional"))
    )
    (net (code "75") (name "unconnected-(B1-Pad50)") (class "Default")
      (node (ref "B1") (pin "50") (pinfunction "50_50") (pintype "bidirectional"))
    )
    (net (code "76") (name "unconnected-(B1-Pad51)") (class "Default")
      (node (ref "B1") (pin "51") (pinfunction "51_51") (pintype "bidirectional"))
    )
    (net (code "77") (name "unconnected-(B1-Pad53)") (class "Default")
      (node (ref "B1") (pin "53") (pinfunction "53_53") (pintype "bidirectional"))
    )
    (net (code "78") (name "unconnected-(B1-PadAREF)") (class "Default")
      (node (ref "B1") (pin "AREF") (pinfunction "AREF_AREF") (pintype "bidirectional"))
    )
    (net (code "79") (name "unconnected-(B1-PadRESET)") (class "Default")
      (node (ref "B1") (pin "RESET") (pinfunction "RESET_RESET") (pintype "bidirectional"))
    )
    (net (code "80") (name "unconnected-(B1-PadVIN)") (class "Default")
      (node (ref "B1") (pin "VIN") (pinfunction "VIN_VIN") (pintype "bidirectional"))
    )
    (net (code "81") (name "unconnected-(ESP-01-GPIO0-PadC1)") (class "Default")
      (node (ref "ESP-01") (pin "C1") (pinfunction "GPIO0_C1") (pintype "bidirectional"))
    )
    (net (code "82") (name "unconnected-(ESP-01-GPIO2-PadB1)") (class "Default")
      (node (ref "ESP-01") (pin "B1") (pinfunction "GPIO2_B1") (pintype "bidirectional"))
    )
  )
)
